# led_boards_easyEDA.net
KiCad netlist of a schematic drawn in EasyEDA
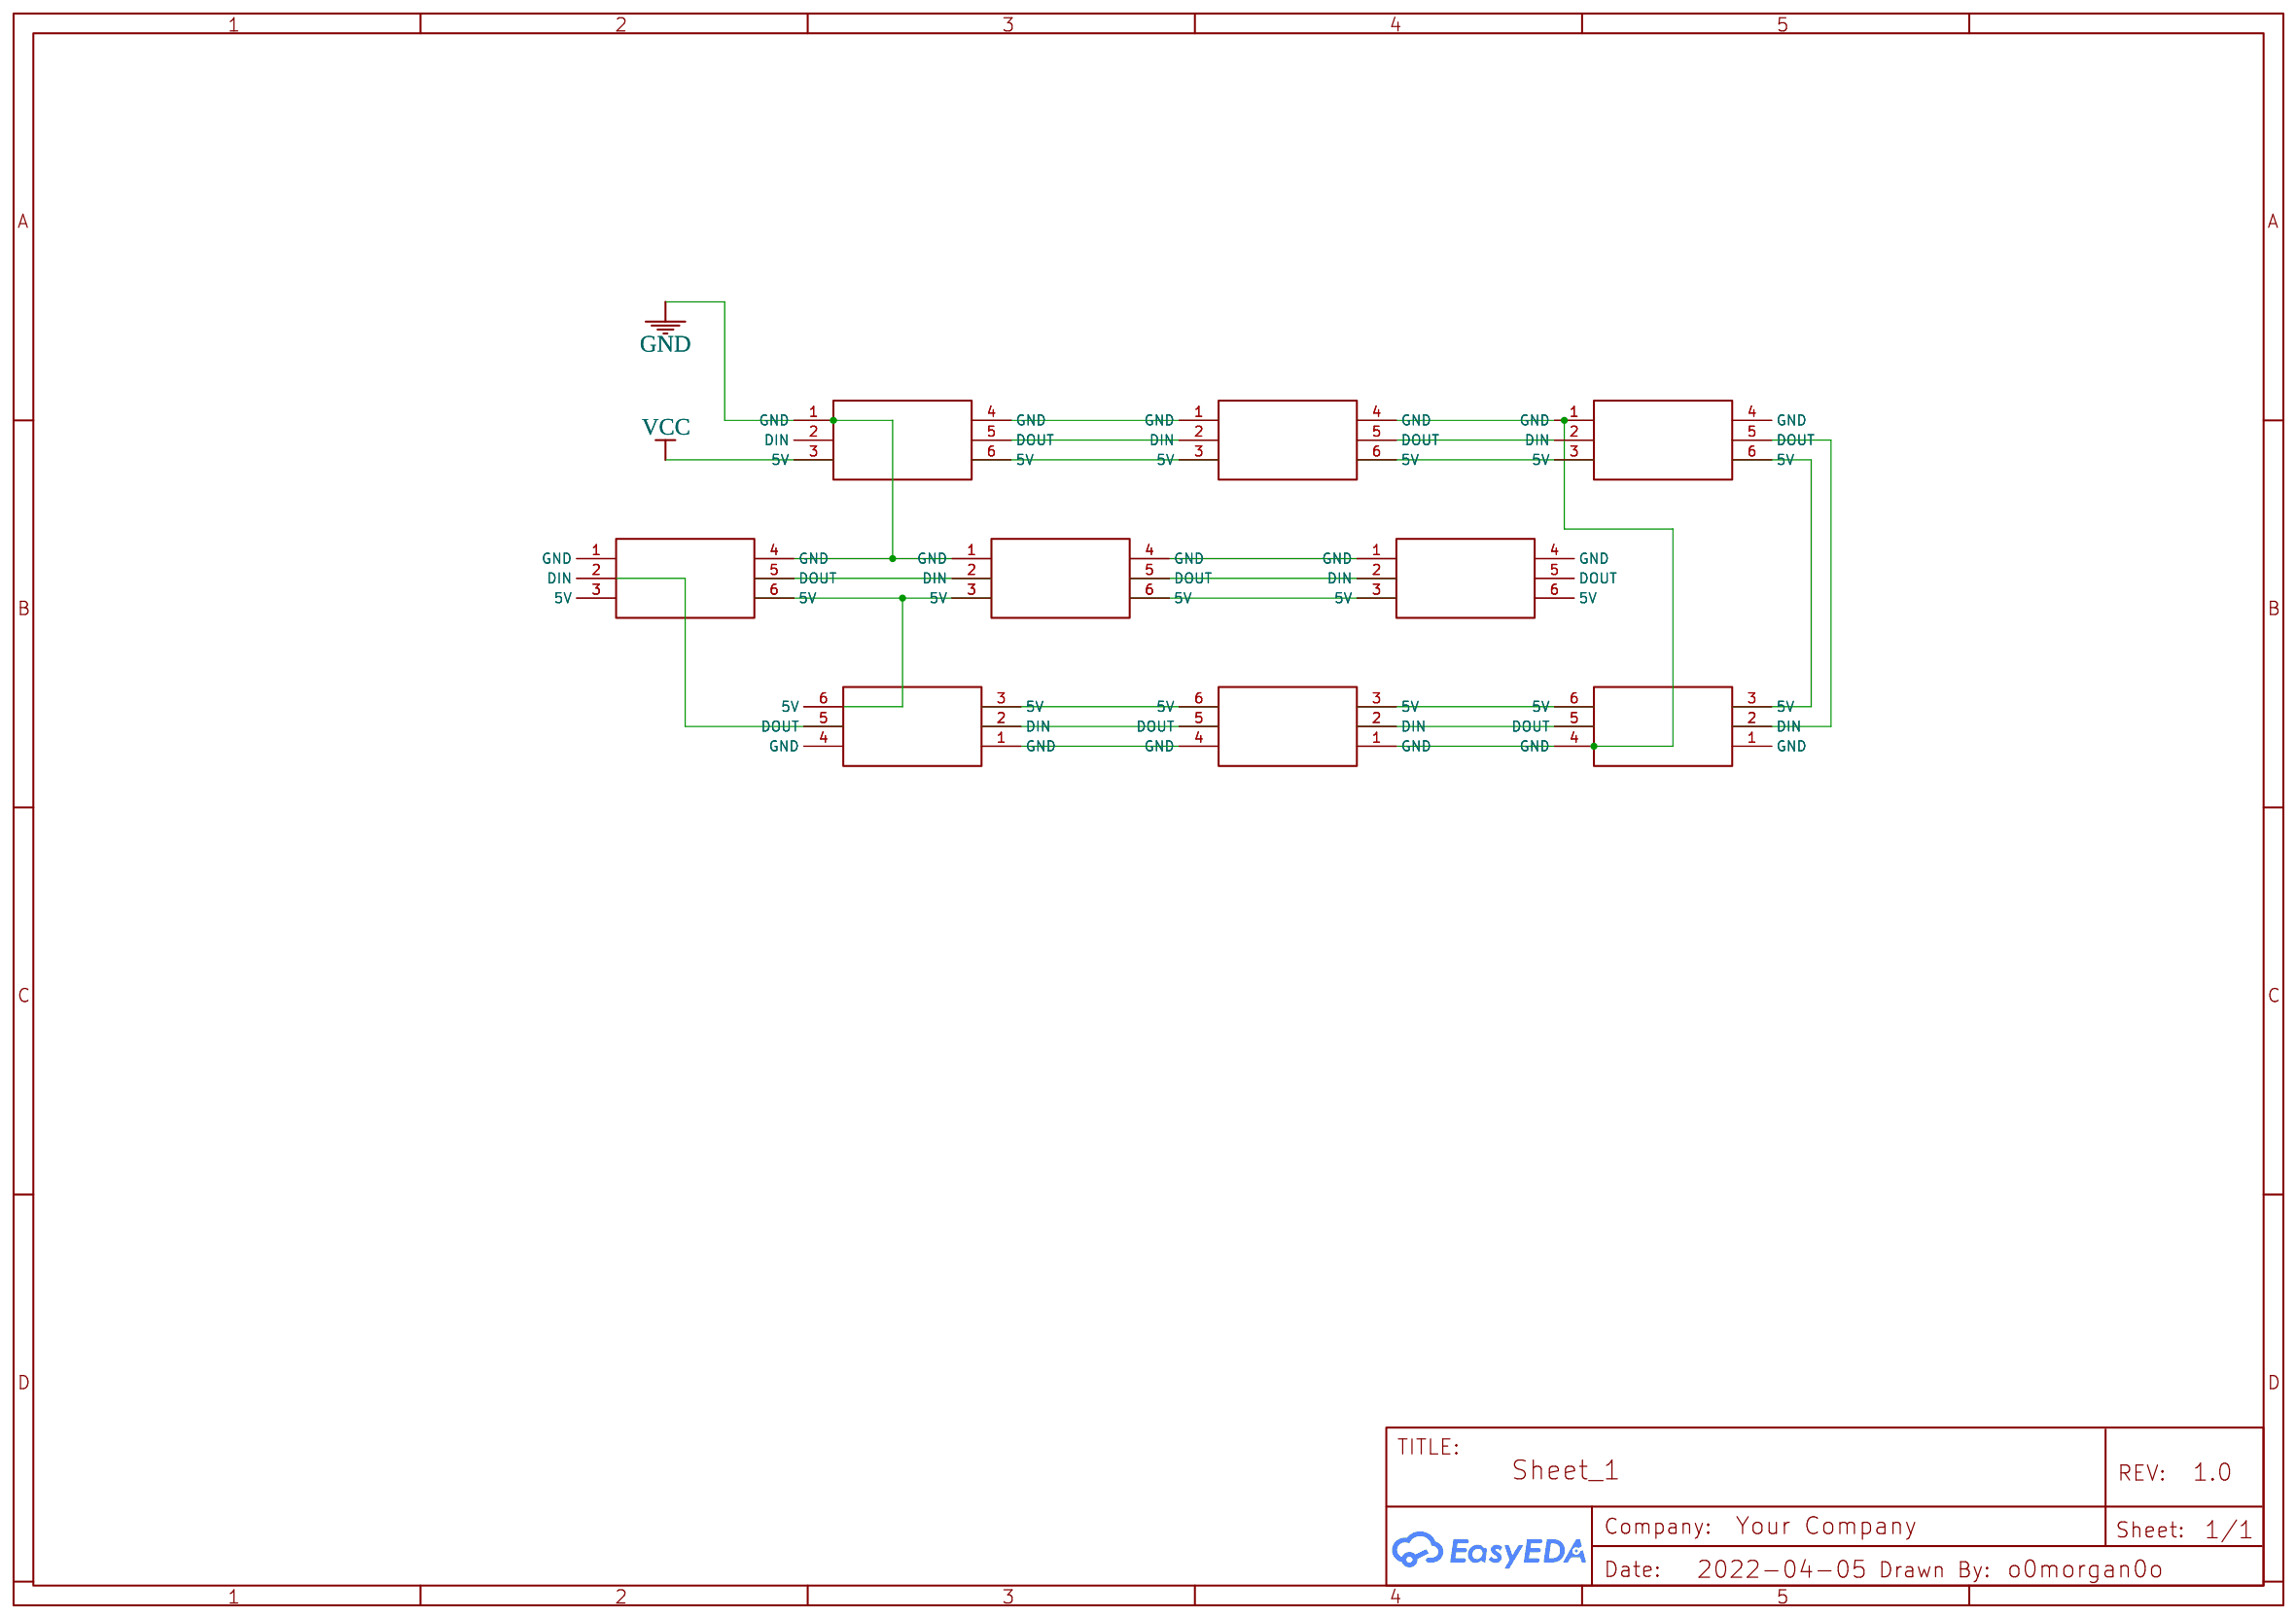
[diagram p0: schematic sheet]

(export (version "E")
  (design (tool "Eeschema 10.0.6"))
  (components
    (comp (ref "U1")
      (value "LED condensed strip single")
      (libsource (lib "") (part "LED condensed strip single"))
    )
    (comp (ref "U2")
      (value "LED condensed strip single")
      (libsource (lib "") (part "LED condensed strip single"))
    )
    (comp (ref "U3")
      (value "LED condensed strip single")
      (libsource (lib "") (part "LED condensed strip single"))
    )
    (comp (ref "U4")
      (value "LED condensed strip single")
      (libsource (lib "") (part "LED condensed strip single"))
    )
    (comp (ref "U5")
      (value "LED condensed strip single")
      (libsource (lib "") (part "LED condensed strip single"))
    )
    (comp (ref "U6")
      (value "LED condensed strip single")
      (libsource (lib "") (part "LED condensed strip single"))
    )
    (comp (ref "U7")
      (value "LED condensed strip single")
      (libsource (lib "") (part "LED condensed strip single_1"))
    )
    (comp (ref "U8")
      (value "LED condensed strip single")
      (libsource (lib "") (part "LED condensed strip single_1"))
    )
    (comp (ref "U9")
      (value "LED condensed strip single")
      (libsource (lib "") (part "LED condensed strip single_1"))
    )
  )
  (nets
    (net (code "1") (name "GND") (class "Default")
      (node (ref "U1") (pin "1") (pinfunction "GND_1") (pintype "unspecified"))
      (node (ref "U2") (pin "4") (pinfunction "GND_4") (pintype "unspecified"))
      (node (ref "U3") (pin "1") (pinfunction "GND_1") (pintype "unspecified"))
    )
    (net (code "2") (name "Net-(U1-5V-Pad6)") (class "Default")
      (node (ref "U1") (pin "6") (pinfunction "5V_6") (pintype "unspecified"))
      (node (ref "U4") (pin "3") (pinfunction "5V_3") (pintype "unspecified"))
    )
    (net (code "3") (name "Net-(U1-DOUT)") (class "Default")
      (node (ref "U1") (pin "5") (pinfunction "DOUT_5") (pintype "unspecified"))
      (node (ref "U4") (pin "2") (pinfunction "DIN_2") (pintype "unspecified"))
    )
    (net (code "4") (name "Net-(U1-GND-Pad4)") (class "Default")
      (node (ref "U1") (pin "4") (pinfunction "GND_4") (pintype "unspecified"))
      (node (ref "U4") (pin "1") (pinfunction "GND_1") (pintype "unspecified"))
    )
    (net (code "5") (name "Net-(U2-5V-Pad6)") (class "Default")
      (node (ref "U2") (pin "6") (pinfunction "5V_6") (pintype "unspecified"))
      (node (ref "U3") (pin "3") (pinfunction "5V_3") (pintype "unspecified"))
      (node (ref "U7") (pin "6") (pinfunction "5V_6") (pintype "unspecified"))
    )
    (net (code "6") (name "Net-(U2-DIN)") (class "Default")
      (node (ref "U2") (pin "2") (pinfunction "DIN_2") (pintype "unspecified"))
      (node (ref "U7") (pin "5") (pinfunction "DOUT_5") (pintype "unspecified"))
    )
    (net (code "7") (name "Net-(U2-DOUT)") (class "Default")
      (node (ref "U2") (pin "5") (pinfunction "DOUT_5") (pintype "unspecified"))
      (node (ref "U3") (pin "2") (pinfunction "DIN_2") (pintype "unspecified"))
    )
    (net (code "8") (name "Net-(U3-5V-Pad6)") (class "Default")
      (node (ref "U3") (pin "6") (pinfunction "5V_6") (pintype "unspecified"))
      (node (ref "U5") (pin "3") (pinfunction "5V_3") (pintype "unspecified"))
    )
    (net (code "9") (name "Net-(U3-DOUT)") (class "Default")
      (node (ref "U3") (pin "5") (pinfunction "DOUT_5") (pintype "unspecified"))
      (node (ref "U5") (pin "2") (pinfunction "DIN_2") (pintype "unspecified"))
    )
    (net (code "10") (name "Net-(U3-GND-Pad4)") (class "Default")
      (node (ref "U3") (pin "4") (pinfunction "GND_4") (pintype "unspecified"))
      (node (ref "U5") (pin "1") (pinfunction "GND_1") (pintype "unspecified"))
    )
    (net (code "11") (name "Net-(U4-5V-Pad6)") (class "Default")
      (node (ref "U4") (pin "6") (pinfunction "5V_6") (pintype "unspecified"))
      (node (ref "U6") (pin "3") (pinfunction "5V_3") (pintype "unspecified"))
    )
    (net (code "12") (name "Net-(U4-DOUT)") (class "Default")
      (node (ref "U4") (pin "5") (pinfunction "DOUT_5") (pintype "unspecified"))
      (node (ref "U6") (pin "2") (pinfunction "DIN_2") (pintype "unspecified"))
    )
    (net (code "13") (name "Net-(U4-GND-Pad4)") (class "Default")
      (node (ref "U4") (pin "4") (pinfunction "GND_4") (pintype "unspecified"))
      (node (ref "U6") (pin "1") (pinfunction "GND_1") (pintype "unspecified"))
      (node (ref "U8") (pin "1") (pinfunction "GND_1") (pintype "unspecified"))
      (node (ref "U9") (pin "4") (pinfunction "GND_4") (pintype "unspecified"))
    )
    (net (code "14") (name "Net-(U6-5V-Pad6)") (class "Default")
      (node (ref "U6") (pin "6") (pinfunction "5V_6") (pintype "unspecified"))
      (node (ref "U9") (pin "3") (pinfunction "5V_3") (pintype "unspecified"))
    )
    (net (code "15") (name "Net-(U6-DOUT)") (class "Default")
      (node (ref "U6") (pin "5") (pinfunction "DOUT_5") (pintype "unspecified"))
      (node (ref "U9") (pin "2") (pinfunction "DIN_2") (pintype "unspecified"))
    )
    (net (code "16") (name "Net-(U7-5V-Pad3)") (class "Default")
      (node (ref "U7") (pin "3") (pinfunction "5V_3") (pintype "unspecified"))
      (node (ref "U8") (pin "6") (pinfunction "5V_6") (pintype "unspecified"))
    )
    (net (code "17") (name "Net-(U7-DIN)") (class "Default")
      (node (ref "U7") (pin "2") (pinfunction "DIN_2") (pintype "unspecified"))
      (node (ref "U8") (pin "5") (pinfunction "DOUT_5") (pintype "unspecified"))
    )
    (net (code "18") (name "Net-(U7-GND-Pad1)") (class "Default")
      (node (ref "U7") (pin "1") (pinfunction "GND_1") (pintype "unspecified"))
      (node (ref "U8") (pin "4") (pinfunction "GND_4") (pintype "unspecified"))
    )
    (net (code "19") (name "Net-(U8-5V-Pad3)") (class "Default")
      (node (ref "U8") (pin "3") (pinfunction "5V_3") (pintype "unspecified"))
      (node (ref "U9") (pin "6") (pinfunction "5V_6") (pintype "unspecified"))
    )
    (net (code "20") (name "Net-(U8-DIN)") (class "Default")
      (node (ref "U8") (pin "2") (pinfunction "DIN_2") (pintype "unspecified"))
      (node (ref "U9") (pin "5") (pinfunction "DOUT_5") (pintype "unspecified"))
    )
    (net (code "21") (name "VCC") (class "Default")
      (node (ref "U1") (pin "3") (pinfunction "5V_3") (pintype "unspecified"))
    )
    (net (code "22") (name "unconnected-(U1-DIN-Pad2)") (class "Default")
      (node (ref "U1") (pin "2") (pinfunction "DIN_2") (pintype "unspecified"))
    )
    (net (code "23") (name "unconnected-(U2-5V-Pad3)") (class "Default")
      (node (ref "U2") (pin "3") (pinfunction "5V_3") (pintype "unspecified"))
    )
    (net (code "24") (name "unconnected-(U2-GND-Pad1)") (class "Default")
      (node (ref "U2") (pin "1") (pinfunction "GND_1") (pintype "unspecified"))
    )
    (net (code "25") (name "unconnected-(U5-5V-Pad6)") (class "Default")
      (node (ref "U5") (pin "6") (pinfunction "5V_6") (pintype "unspecified"))
    )
    (net (code "26") (name "unconnected-(U5-DOUT-Pad5)") (class "Default")
      (node (ref "U5") (pin "5") (pinfunction "DOUT_5") (pintype "unspecified"))
    )
    (net (code "27") (name "unconnected-(U5-GND-Pad4)") (class "Default")
      (node (ref "U5") (pin "4") (pinfunction "GND_4") (pintype "unspecified"))
    )
    (net (code "28") (name "unconnected-(U6-GND-Pad4)") (class "Default")
      (node (ref "U6") (pin "4") (pinfunction "GND_4") (pintype "unspecified"))
    )
    (net (code "29") (name "unconnected-(U7-GND-Pad4)") (class "Default")
      (node (ref "U7") (pin "4") (pinfunction "GND_4") (pintype "unspecified"))
    )
    (net (code "30") (name "unconnected-(U9-GND-Pad1)") (class "Default")
      (node (ref "U9") (pin "1") (pinfunction "GND_1") (pintype "unspecified"))
    )
  )
)
